# arduinoBaseboard.net
KiCad netlist of a schematic drawn in EAGLE
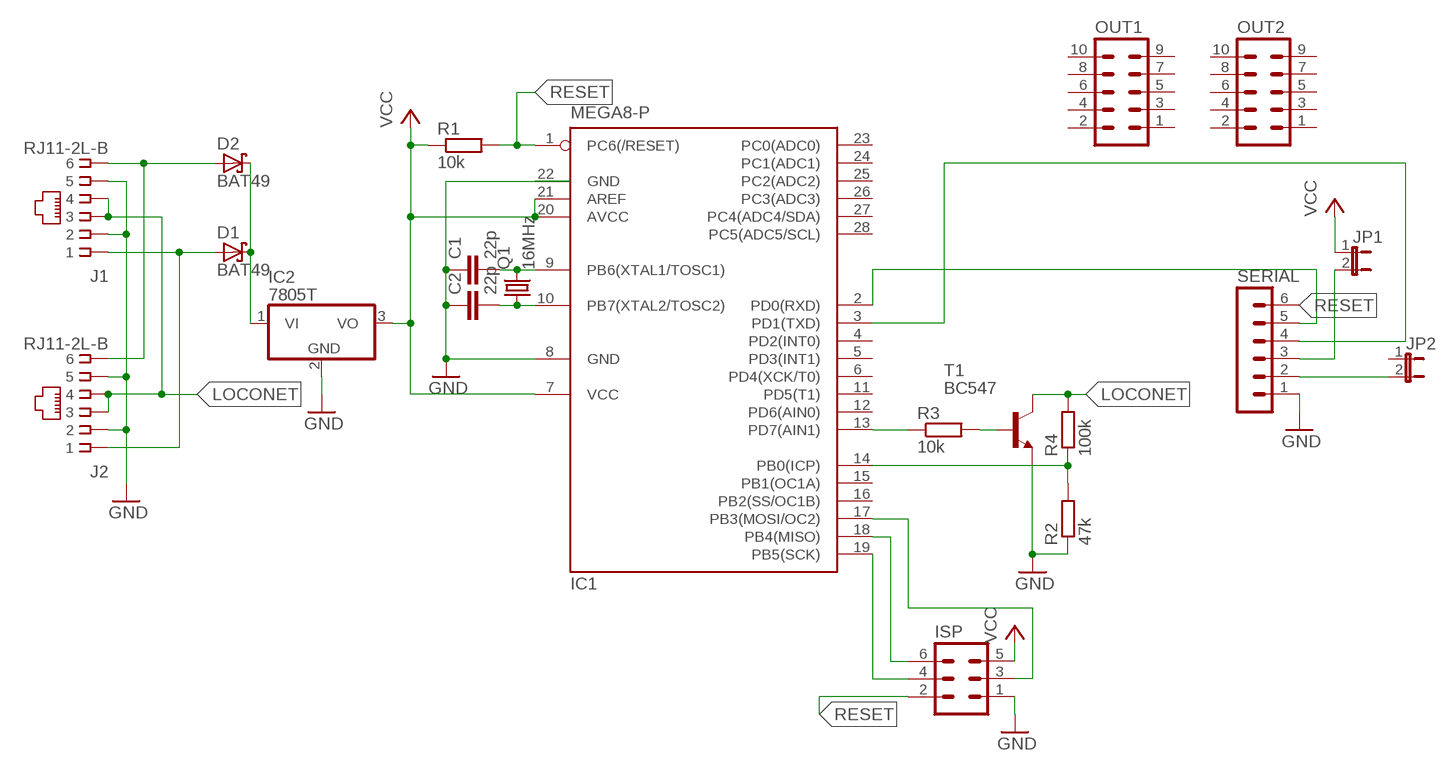
[diagram p0: schematic, sheet 1]

(export (version "E")
  (design (tool "Eeschema 10.0.6"))
  (components
    (comp (ref "C1")
      (value "22p")
      (footprint "eagle-import:C025-024X044")
      (libsource (lib "eagle-import") (part "C-EU025-024X044"))
    )
    (comp (ref "C2")
      (value "22p")
      (footprint "eagle-import:C025-024X044")
      (libsource (lib "eagle-import") (part "C-EU025-024X044"))
    )
    (comp (ref "D1")
      (value "BAT49")
      (footprint "eagle-import:DO41-10")
      (libsource (lib "eagle-import") (part "BAT49"))
    )
    (comp (ref "D2")
      (value "BAT49")
      (footprint "eagle-import:DO41-10")
      (libsource (lib "eagle-import") (part "BAT49"))
    )
    (comp (ref "IC1")
      (value "MEGA8-P")
      (footprint "eagle-import:DIL28-3")
      (libsource (lib "eagle-import") (part "MEGA8-P"))
    )
    (comp (ref "IC2")
      (value "7805T")
      (footprint "eagle-import:TO220H")
      (libsource (lib "eagle-import") (part "78T05"))
    )
    (comp (ref "ISP")
      (value "MA03-2")
      (footprint "eagle-import:MA03-2")
      (libsource (lib "eagle-import") (part "MA03-2"))
    )
    (comp (ref "J1")
      (value "RJ11-2L-B")
      (footprint "eagle-import:RJ11-NO_SHIELD")
      (fields (field (name "MF") "TYCO ELECTRONICS"))
      (libsource (lib "eagle-import") (part "RJ11-2L-B"))
    )
    (comp (ref "J2")
      (value "RJ11-2L-B")
      (footprint "eagle-import:RJ11-NO_SHIELD")
      (fields (field (name "MF") "TYCO ELECTRONICS"))
      (libsource (lib "eagle-import") (part "RJ11-2L-B"))
    )
    (comp (ref "JP1")
      (value "JP1E")
      (footprint "eagle-import:JP1")
      (libsource (lib "eagle-import") (part "JP1E"))
    )
    (comp (ref "JP2")
      (value "JP1E")
      (footprint "eagle-import:JP1")
      (libsource (lib "eagle-import") (part "JP1E"))
    )
    (comp (ref "OUT1")
      (value "MA05-2")
      (footprint "eagle-import:MA05-2")
      (libsource (lib "eagle-import") (part "MA05-2"))
    )
    (comp (ref "OUT2")
      (value "MA05-2")
      (footprint "eagle-import:MA05-2")
      (libsource (lib "eagle-import") (part "MA05-2"))
    )
    (comp (ref "Q1")
      (value "16MHz")
      (footprint "eagle-import:HC49_S")
      (libsource (lib "eagle-import") (part "CRYSTALHC49S"))
    )
    (comp (ref "R1")
      (value "10k")
      (footprint "eagle-import:0204_7")
      (libsource (lib "eagle-import") (part "R-EU_0204/7"))
    )
    (comp (ref "R2")
      (value "47k")
      (footprint "eagle-import:0204_7")
      (libsource (lib "eagle-import") (part "R-EU_0204/7"))
    )
    (comp (ref "R3")
      (value "10k")
      (footprint "eagle-import:0204_7")
      (libsource (lib "eagle-import") (part "R-EU_0204/7"))
    )
    (comp (ref "R4")
      (value "100k")
      (footprint "eagle-import:0204_7")
      (libsource (lib "eagle-import") (part "R-EU_0204/7"))
    )
    (comp (ref "SERIAL")
      (value "MA06-1")
      (footprint "eagle-import:MA06-1")
      (libsource (lib "eagle-import") (part "MA06-1"))
    )
    (comp (ref "T1")
      (value "BC547")
      (footprint "eagle-import:TO92")
      (libsource (lib "eagle-import") (part "BC547"))
    )
  )
  (nets
    (net (code "1") (name "GND") (class "Default")
      (node (ref "C1") (pin "1") (pinfunction "1_1") (pintype "passive"))
      (node (ref "C2") (pin "1") (pinfunction "1_1") (pintype "passive"))
      (node (ref "IC1") (pin "22") (pinfunction "GND_22") (pintype "power_in"))
      (node (ref "IC1") (pin "8") (pinfunction "GND_8") (pintype "power_in"))
      (node (ref "IC2") (pin "2") (pinfunction "GND_2") (pintype "passive"))
      (node (ref "ISP") (pin "1") (pinfunction "1_1") (pintype "passive"))
      (node (ref "J1") (pin "2") (pinfunction "2_2") (pintype "passive"))
      (node (ref "J1") (pin "5") (pinfunction "5_5") (pintype "passive"))
      (node (ref "J2") (pin "2") (pinfunction "2_2") (pintype "passive"))
      (node (ref "J2") (pin "5") (pinfunction "5_5") (pintype "passive"))
      (node (ref "R2") (pin "1") (pinfunction "1_1") (pintype "passive"))
      (node (ref "SERIAL") (pin "1") (pinfunction "1_1") (pintype "passive"))
      (node (ref "T1") (pin "1") (pinfunction "E_1") (pintype "passive"))
    )
    (net (code "2") (name "LOCONET") (class "Default")
      (node (ref "J1") (pin "3") (pinfunction "3_3") (pintype "passive"))
      (node (ref "J1") (pin "4") (pinfunction "4_4") (pintype "passive"))
      (node (ref "J2") (pin "3") (pinfunction "3_3") (pintype "passive"))
      (node (ref "J2") (pin "4") (pinfunction "4_4") (pintype "passive"))
      (node (ref "R4") (pin "2") (pinfunction "2_2") (pintype "passive"))
      (node (ref "T1") (pin "3") (pinfunction "C_3") (pintype "passive"))
    )
    (net (code "3") (name "Net-(D1-PadA)") (class "Default")
      (node (ref "D1") (pin "A") (pinfunction "A_A") (pintype "passive"))
      (node (ref "J1") (pin "1") (pinfunction "1_1") (pintype "passive"))
      (node (ref "J2") (pin "1") (pinfunction "1_1") (pintype "passive"))
    )
    (net (code "4") (name "Net-(D2-PadA)") (class "Default")
      (node (ref "D2") (pin "A") (pinfunction "A_A") (pintype "passive"))
      (node (ref "J1") (pin "6") (pinfunction "6_6") (pintype "passive"))
      (node (ref "J2") (pin "6") (pinfunction "6_6") (pintype "passive"))
    )
    (net (code "5") (name "Net-(IC1-PB0(ICP))") (class "Default")
      (node (ref "IC1") (pin "14") (pinfunction "PB0(ICP)_14") (pintype "bidirectional"))
      (node (ref "R2") (pin "2") (pinfunction "2_2") (pintype "passive"))
      (node (ref "R4") (pin "1") (pinfunction "1_1") (pintype "passive"))
    )
    (net (code "6") (name "Net-(IC1-PB3(MOSI{slash}OC2))") (class "Default")
      (node (ref "IC1") (pin "17") (pinfunction "PB3(MOSI/OC2)_17") (pintype "bidirectional"))
      (node (ref "ISP") (pin "3") (pinfunction "3_3") (pintype "passive"))
    )
    (net (code "7") (name "Net-(IC1-PB4(MISO))") (class "Default")
      (node (ref "IC1") (pin "18") (pinfunction "PB4(MISO)_18") (pintype "bidirectional"))
      (node (ref "ISP") (pin "6") (pinfunction "6_6") (pintype "passive"))
    )
    (net (code "8") (name "Net-(IC1-PB5(SCK))") (class "Default")
      (node (ref "IC1") (pin "19") (pinfunction "PB5(SCK)_19") (pintype "bidirectional"))
      (node (ref "ISP") (pin "4") (pinfunction "4_4") (pintype "passive"))
    )
    (net (code "9") (name "Net-(IC1-PB6(XTAL1{slash}TOSC1))") (class "Default")
      (node (ref "C1") (pin "2") (pinfunction "2_2") (pintype "passive"))
      (node (ref "IC1") (pin "9") (pinfunction "PB6(XTAL1/TOSC1)_9") (pintype "bidirectional"))
      (node (ref "Q1") (pin "2") (pinfunction "2_2") (pintype "passive"))
    )
    (net (code "10") (name "Net-(IC1-PB7(XTAL2{slash}TOSC2))") (class "Default")
      (node (ref "C2") (pin "2") (pinfunction "2_2") (pintype "passive"))
      (node (ref "IC1") (pin "10") (pinfunction "PB7(XTAL2/TOSC2)_10") (pintype "bidirectional"))
      (node (ref "Q1") (pin "1") (pinfunction "1_1") (pintype "passive"))
    )
    (net (code "11") (name "Net-(IC1-PD0(RXD))") (class "Default")
      (node (ref "IC1") (pin "2") (pinfunction "PD0(RXD)_2") (pintype "bidirectional"))
      (node (ref "SERIAL") (pin "5") (pinfunction "5_5") (pintype "passive"))
    )
    (net (code "12") (name "Net-(IC1-PD1(TXD))") (class "Default")
      (node (ref "IC1") (pin "3") (pinfunction "PD1(TXD)_3") (pintype "bidirectional"))
      (node (ref "SERIAL") (pin "4") (pinfunction "4_4") (pintype "passive"))
    )
    (net (code "13") (name "Net-(IC1-PD7(AIN1))") (class "Default")
      (node (ref "IC1") (pin "13") (pinfunction "PD7(AIN1)_13") (pintype "bidirectional"))
      (node (ref "R3") (pin "1") (pinfunction "1_1") (pintype "passive"))
    )
    (net (code "14") (name "Net-(IC2-VI)") (class "Default")
      (node (ref "D1") (pin "C") (pinfunction "C_C") (pintype "passive"))
      (node (ref "D2") (pin "C") (pinfunction "C_C") (pintype "passive"))
      (node (ref "IC2") (pin "1") (pinfunction "VI_1") (pintype "input"))
    )
    (net (code "15") (name "Net-(JP2-Pad2)") (class "Default")
      (node (ref "JP2") (pin "2") (pinfunction "2_2") (pintype "passive"))
      (node (ref "SERIAL") (pin "2") (pinfunction "2_2") (pintype "passive"))
    )
    (net (code "16") (name "Net-(T1-B)") (class "Default")
      (node (ref "R3") (pin "2") (pinfunction "2_2") (pintype "passive"))
      (node (ref "T1") (pin "2") (pinfunction "B_2") (pintype "passive"))
    )
    (net (code "17") (name "RESET") (class "Default")
      (node (ref "IC1") (pin "1") (pinfunction "PC6(/RESET)_1") (pintype "bidirectional"))
      (node (ref "ISP") (pin "2") (pinfunction "2_2") (pintype "passive"))
      (node (ref "JP1") (pin "2") (pinfunction "2_2") (pintype "passive"))
      (node (ref "R1") (pin "2") (pinfunction "2_2") (pintype "passive"))
      (node (ref "SERIAL") (pin "3") (pinfunction "3_3") (pintype "passive"))
    )
    (net (code "18") (name "VCC") (class "Default")
      (node (ref "IC1") (pin "20") (pinfunction "AVCC_20") (pintype "power_in"))
      (node (ref "IC1") (pin "21") (pinfunction "AREF_21") (pintype "passive"))
      (node (ref "IC1") (pin "7") (pinfunction "VCC_7") (pintype "power_in"))
      (node (ref "IC2") (pin "3") (pinfunction "VO_3") (pintype "passive"))
      (node (ref "ISP") (pin "5") (pinfunction "5_5") (pintype "passive"))
      (node (ref "JP1") (pin "1") (pinfunction "1_1") (pintype "passive"))
      (node (ref "R1") (pin "1") (pinfunction "1_1") (pintype "passive"))
    )
    (net (code "19") (name "unconnected-(IC1-PB1(OC1A)-Pad15)") (class "Default")
      (node (ref "IC1") (pin "15") (pinfunction "PB1(OC1A)_15") (pintype "bidirectional"))
    )
    (net (code "20") (name "unconnected-(IC1-PB2(SS{slash}OC1B)-Pad16)") (class "Default")
      (node (ref "IC1") (pin "16") (pinfunction "PB2(SS/OC1B)_16") (pintype "bidirectional"))
    )
    (net (code "21") (name "unconnected-(IC1-PC0(ADC0)-Pad23)") (class "Default")
      (node (ref "IC1") (pin "23") (pinfunction "PC0(ADC0)_23") (pintype "bidirectional"))
    )
    (net (code "22") (name "unconnected-(IC1-PC1(ADC1)-Pad24)") (class "Default")
      (node (ref "IC1") (pin "24") (pinfunction "PC1(ADC1)_24") (pintype "bidirectional"))
    )
    (net (code "23") (name "unconnected-(IC1-PC2(ADC2)-Pad25)") (class "Default")
      (node (ref "IC1") (pin "25") (pinfunction "PC2(ADC2)_25") (pintype "bidirectional"))
    )
    (net (code "24") (name "unconnected-(IC1-PC3(ADC3)-Pad26)") (class "Default")
      (node (ref "IC1") (pin "26") (pinfunction "PC3(ADC3)_26") (pintype "bidirectional"))
    )
    (net (code "25") (name "unconnected-(IC1-PC4(ADC4{slash}SDA)-Pad27)") (class "Default")
      (node (ref "IC1") (pin "27") (pinfunction "PC4(ADC4/SDA)_27") (pintype "bidirectional"))
    )
    (net (code "26") (name "unconnected-(IC1-PC5(ADC5{slash}SCL)-Pad28)") (class "Default")
      (node (ref "IC1") (pin "28") (pinfunction "PC5(ADC5/SCL)_28") (pintype "bidirectional"))
    )
    (net (code "27") (name "unconnected-(IC1-PD2(INT0)-Pad4)") (class "Default")
      (node (ref "IC1") (pin "4") (pinfunction "PD2(INT0)_4") (pintype "bidirectional"))
    )
    (net (code "28") (name "unconnected-(IC1-PD3(INT1)-Pad5)") (class "Default")
      (node (ref "IC1") (pin "5") (pinfunction "PD3(INT1)_5") (pintype "bidirectional"))
    )
    (net (code "29") (name "unconnected-(IC1-PD4(XCK{slash}T0)-Pad6)") (class "Default")
      (node (ref "IC1") (pin "6") (pinfunction "PD4(XCK/T0)_6") (pintype "bidirectional"))
    )
    (net (code "30") (name "unconnected-(IC1-PD5(T1)-Pad11)") (class "Default")
      (node (ref "IC1") (pin "11") (pinfunction "PD5(T1)_11") (pintype "bidirectional"))
    )
    (net (code "31") (name "unconnected-(IC1-PD6(AIN0)-Pad12)") (class "Default")
      (node (ref "IC1") (pin "12") (pinfunction "PD6(AIN0)_12") (pintype "bidirectional"))
    )
    (net (code "32") (name "unconnected-(JP2-Pad1)") (class "Default")
      (node (ref "JP2") (pin "1") (pinfunction "1_1") (pintype "passive"))
    )
    (net (code "33") (name "unconnected-(OUT1-Pad1)") (class "Default")
      (node (ref "OUT1") (pin "1") (pinfunction "1_1") (pintype "passive"))
    )
    (net (code "34") (name "unconnected-(OUT1-Pad2)") (class "Default")
      (node (ref "OUT1") (pin "2") (pinfunction "2_2") (pintype "passive"))
    )
    (net (code "35") (name "unconnected-(OUT1-Pad3)") (class "Default")
      (node (ref "OUT1") (pin "3") (pinfunction "3_3") (pintype "passive"))
    )
    (net (code "36") (name "unconnected-(OUT1-Pad4)") (class "Default")
      (node (ref "OUT1") (pin "4") (pinfunction "4_4") (pintype "passive"))
    )
    (net (code "37") (name "unconnected-(OUT1-Pad5)") (class "Default")
      (node (ref "OUT1") (pin "5") (pinfunction "5_5") (pintype "passive"))
    )
    (net (code "38") (name "unconnected-(OUT1-Pad6)") (class "Default")
      (node (ref "OUT1") (pin "6") (pinfunction "6_6") (pintype "passive"))
    )
    (net (code "39") (name "unconnected-(OUT1-Pad7)") (class "Default")
      (node (ref "OUT1") (pin "7") (pinfunction "7_7") (pintype "passive"))
    )
    (net (code "40") (name "unconnected-(OUT1-Pad8)") (class "Default")
      (node (ref "OUT1") (pin "8") (pinfunction "8_8") (pintype "passive"))
    )
    (net (code "41") (name "unconnected-(OUT1-Pad9)") (class "Default")
      (node (ref "OUT1") (pin "9") (pinfunction "9_9") (pintype "passive"))
    )
    (net (code "42") (name "unconnected-(OUT1-Pad10)") (class "Default")
      (node (ref "OUT1") (pin "10") (pinfunction "10_10") (pintype "passive"))
    )
    (net (code "43") (name "unconnected-(OUT2-Pad1)") (class "Default")
      (node (ref "OUT2") (pin "1") (pinfunction "1_1") (pintype "passive"))
    )
    (net (code "44") (name "unconnected-(OUT2-Pad2)") (class "Default")
      (node (ref "OUT2") (pin "2") (pinfunction "2_2") (pintype "passive"))
    )
    (net (code "45") (name "unconnected-(OUT2-Pad3)") (class "Default")
      (node (ref "OUT2") (pin "3") (pinfunction "3_3") (pintype "passive"))
    )
    (net (code "46") (name "unconnected-(OUT2-Pad4)") (class "Default")
      (node (ref "OUT2") (pin "4") (pinfunction "4_4") (pintype "passive"))
    )
    (net (code "47") (name "unconnected-(OUT2-Pad5)") (class "Default")
      (node (ref "OUT2") (pin "5") (pinfunction "5_5") (pintype "passive"))
    )
    (net (code "48") (name "unconnected-(OUT2-Pad6)") (class "Default")
      (node (ref "OUT2") (pin "6") (pinfunction "6_6") (pintype "passive"))
    )
    (net (code "49") (name "unconnected-(OUT2-Pad7)") (class "Default")
      (node (ref "OUT2") (pin "7") (pinfunction "7_7") (pintype "passive"))
    )
    (net (code "50") (name "unconnected-(OUT2-Pad8)") (class "Default")
      (node (ref "OUT2") (pin "8") (pinfunction "8_8") (pintype "passive"))
    )
    (net (code "51") (name "unconnected-(OUT2-Pad9)") (class "Default")
      (node (ref "OUT2") (pin "9") (pinfunction "9_9") (pintype "passive"))
    )
    (net (code "52") (name "unconnected-(OUT2-Pad10)") (class "Default")
      (node (ref "OUT2") (pin "10") (pinfunction "10_10") (pintype "passive"))
    )
    (net (code "53") (name "unconnected-(SERIAL-Pad6)") (class "Default")
      (node (ref "SERIAL") (pin "6") (pinfunction "6_6") (pintype "passive"))
    )
  )
)
